# Ethernet.net
KiCad netlist of a schematic drawn in Altium Designer
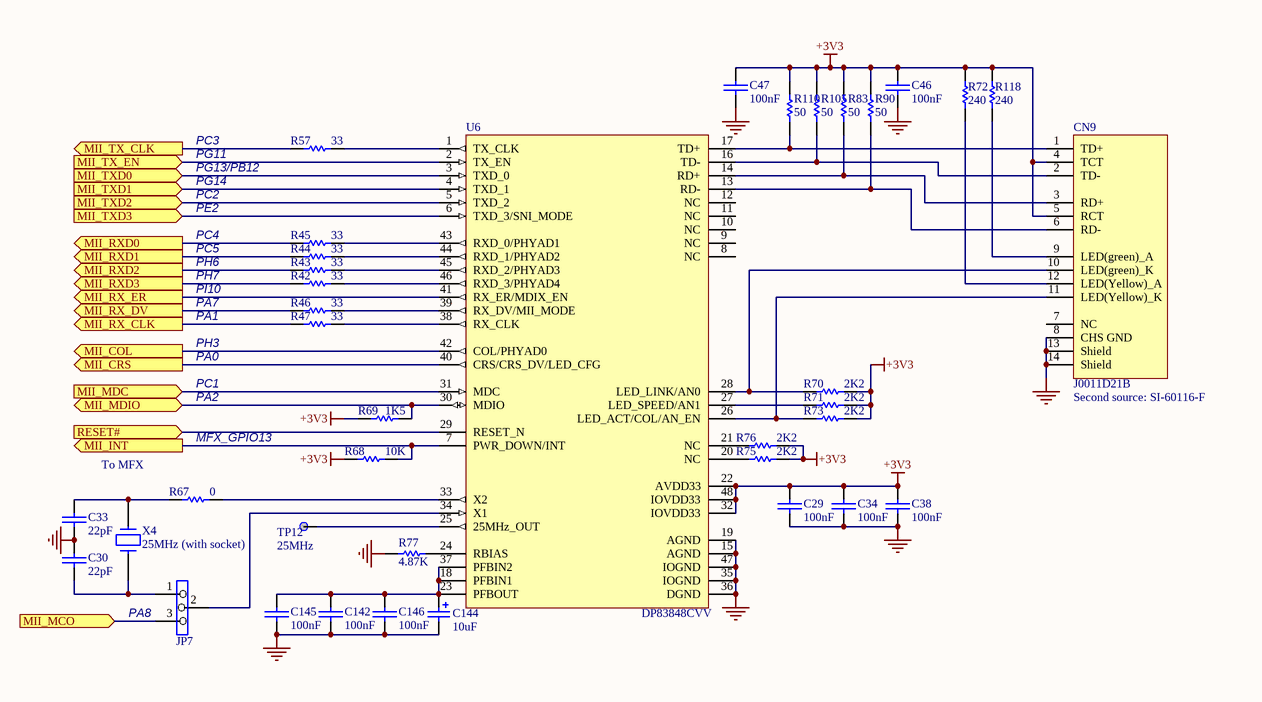
[diagram p0: Ethernet.SchDoc]

(export (version "E")
  (design (tool "Eeschema 10.0.6"))
  (components
    (comp (ref "C29")
      (value "100nF")
      (footprint "0603C")
      (description "Capacitor")
      (libsource (lib "*") (part "CAP"))
    )
    (comp (ref "C30")
      (value "22pF")
      (footprint "0603C")
      (description "Capacitor")
      (libsource (lib "*") (part "CAP"))
    )
    (comp (ref "C33")
      (value "22pF")
      (footprint "0603C")
      (description "Capacitor")
      (libsource (lib "*") (part "CAP"))
    )
    (comp (ref "C34")
      (value "100nF")
      (footprint "0603C")
      (description "Capacitor")
      (libsource (lib "*") (part "CAP"))
    )
    (comp (ref "C38")
      (value "100nF")
      (footprint "0603C")
      (description "Capacitor")
      (libsource (lib "*") (part "CAP"))
    )
    (comp (ref "C46")
      (value "100nF")
      (footprint "0603C")
      (description "Capacitor")
      (libsource (lib "*") (part "CAP"))
    )
    (comp (ref "C47")
      (value "100nF")
      (footprint "0603C")
      (description "Capacitor")
      (libsource (lib "*") (part "CAP"))
    )
    (comp (ref "C142")
      (value "100nF")
      (footprint "0603C")
      (description "Capacitor")
      (libsource (lib "*") (part "CAP"))
    )
    (comp (ref "C144")
      (value "10uF")
      (footprint "TAN-A")
      (description "Polarized Capacitor (Radial)")
      (fields (field (name "PUBLISHER") "Altium Limited"))
      (libsource (lib "Miscellaneous Devices") (part "Cap Pol1"))
    )
    (comp (ref "C145")
      (value "100nF")
      (footprint "0603C")
      (description "Capacitor")
      (libsource (lib "*") (part "CAP"))
    )
    (comp (ref "C146")
      (value "100nF")
      (footprint "0603C")
      (description "Capacitor")
      (libsource (lib "*") (part "CAP"))
    )
    (comp (ref "CN9")
      (value "J0011D21B")
      (footprint "RJ45_J0011D01BNL")
      (libsource (lib "MB784") (part "J0011D21B"))
    )
    (comp (ref "JP7") (value "~") (footprint "SIP3") (libsource (lib "STR910_SCHLIB") (part "Jumper3")))
    (comp (ref "R42")
      (value "33")
      (footprint "0603R")
      (description "Resistor")
      (fields (field (name "PUBLISHER") "Altium Limited"))
      (libsource (lib "Miscellaneous Devices") (part "Res1"))
    )
    (comp (ref "R43")
      (value "33")
      (footprint "0603R")
      (description "Resistor")
      (fields (field (name "PUBLISHER") "Altium Limited"))
      (libsource (lib "Miscellaneous Devices") (part "Res1"))
    )
    (comp (ref "R44")
      (value "33")
      (footprint "0603R")
      (description "Resistor")
      (fields (field (name "PUBLISHER") "Altium Limited"))
      (libsource (lib "Miscellaneous Devices") (part "Res1"))
    )
    (comp (ref "R45")
      (value "33")
      (footprint "0603R")
      (description "Resistor")
      (fields (field (name "PUBLISHER") "Altium Limited"))
      (libsource (lib "Miscellaneous Devices") (part "Res1"))
    )
    (comp (ref "R46")
      (value "33")
      (footprint "0603R")
      (description "Resistor")
      (fields (field (name "PUBLISHER") "Altium Limited"))
      (libsource (lib "Miscellaneous Devices") (part "Res1"))
    )
    (comp (ref "R47")
      (value "33")
      (footprint "0603R")
      (description "Resistor")
      (fields (field (name "PUBLISHER") "Altium Limited"))
      (libsource (lib "Miscellaneous Devices") (part "Res1"))
    )
    (comp (ref "R57")
      (value "33")
      (footprint "0603R")
      (description "Resistor")
      (fields (field (name "PUBLISHER") "Altium Limited"))
      (libsource (lib "Miscellaneous Devices") (part "Res1"))
    )
    (comp (ref "R67")
      (value "0")
      (footprint "0603R")
      (description "Resistor")
      (fields (field (name "PUBLISHER") "Altium Limited"))
      (libsource (lib "Miscellaneous Devices") (part "Res1"))
    )
    (comp (ref "R68")
      (value "10K")
      (footprint "0603R")
      (description "Resistor")
      (fields (field (name "PUBLISHER") "Altium Limited"))
      (libsource (lib "Miscellaneous Devices") (part "Res1"))
    )
    (comp (ref "R69")
      (value "1K5")
      (footprint "0603R")
      (description "Resistor")
      (fields (field (name "PUBLISHER") "Altium Limited"))
      (libsource (lib "Miscellaneous Devices") (part "Res1"))
    )
    (comp (ref "R70")
      (value "2K2")
      (footprint "0603R")
      (description "Resistor")
      (fields (field (name "PUBLISHER") "Altium Limited"))
      (libsource (lib "Miscellaneous Devices") (part "Res1"))
    )
    (comp (ref "R71")
      (value "2K2")
      (footprint "0603R")
      (description "Resistor")
      (fields (field (name "PUBLISHER") "Altium Limited"))
      (libsource (lib "Miscellaneous Devices") (part "Res1"))
    )
    (comp (ref "R72")
      (value "240")
      (footprint "0603R")
      (description "Resistor")
      (fields (field (name "PUBLISHER") "Altium Limited"))
      (libsource (lib "Miscellaneous Devices") (part "Res1"))
    )
    (comp (ref "R73")
      (value "2K2")
      (footprint "0603R")
      (description "Resistor")
      (fields (field (name "PUBLISHER") "Altium Limited"))
      (libsource (lib "Miscellaneous Devices") (part "Res1"))
    )
    (comp (ref "R75")
      (value "2K2")
      (footprint "0603R")
      (description "Resistor")
      (fields (field (name "PUBLISHER") "Altium Limited"))
      (libsource (lib "Miscellaneous Devices") (part "Res1"))
    )
    (comp (ref "R76")
      (value "2K2")
      (footprint "0603R")
      (description "Resistor")
      (fields (field (name "PUBLISHER") "Altium Limited"))
      (libsource (lib "Miscellaneous Devices") (part "Res1"))
    )
    (comp (ref "R77")
      (value "4.87K")
      (footprint "0603R")
      (description "Resistor")
      (fields (field (name "PUBLISHER") "Altium Limited"))
      (libsource (lib "Miscellaneous Devices") (part "Res1"))
    )
    (comp (ref "R83")
      (value "50")
      (footprint "0603R")
      (description "Resistor")
      (fields (field (name "PUBLISHER") "Altium Limited"))
      (libsource (lib "Miscellaneous Devices") (part "Res1"))
    )
    (comp (ref "R90")
      (value "50")
      (footprint "0603R")
      (description "Resistor")
      (fields (field (name "PUBLISHER") "Altium Limited"))
      (libsource (lib "Miscellaneous Devices") (part "Res1"))
    )
    (comp (ref "R105")
      (value "50")
      (footprint "0603R")
      (description "Resistor")
      (fields (field (name "PUBLISHER") "Altium Limited"))
      (libsource (lib "Miscellaneous Devices") (part "Res1"))
    )
    (comp (ref "R110")
      (value "50")
      (footprint "0603R")
      (description "Resistor")
      (fields (field (name "PUBLISHER") "Altium Limited"))
      (libsource (lib "Miscellaneous Devices") (part "Res1"))
    )
    (comp (ref "R118")
      (value "240")
      (footprint "0603R")
      (description "Resistor")
      (fields (field (name "PUBLISHER") "Altium Limited"))
      (libsource (lib "Miscellaneous Devices") (part "Res1"))
    )
    (comp (ref "TP12") (value "25MHz") (footprint "TP") (libsource (lib "*") (part "TP")))
    (comp (ref "U6")
      (value "DP83848CVV")
      (footprint "LQFP48_0R5_9X9")
      (libsource (lib "MB784") (part "DP83848CVV"))
    )
    (comp (ref "X4")
      (value "25MHz (with socket)")
      (footprint "XTAL_socket")
      (description "Crystal")
      (libsource (lib "*") (part "CRYSTAL"))
    )
  )
  (nets
    (net (code "1") (name "+3V3") (class "Default")
      (node (ref "C29") (pin "1") (pinfunction "1_1") (pintype "passive"))
      (node (ref "C34") (pin "2") (pinfunction "2_2") (pintype "passive"))
      (node (ref "C38") (pin "2") (pinfunction "2_2") (pintype "passive"))
      (node (ref "C46") (pin "2") (pinfunction "2_2") (pintype "passive"))
      (node (ref "C47") (pin "2") (pinfunction "2_2") (pintype "passive"))
      (node (ref "CN9") (pin "4") (pinfunction "TCT_4") (pintype "passive"))
      (node (ref "CN9") (pin "5") (pinfunction "RCT_5") (pintype "passive"))
      (node (ref "R105") (pin "1") (pinfunction "1_1") (pintype "passive"))
      (node (ref "R110") (pin "1") (pinfunction "1_1") (pintype "passive"))
      (node (ref "R118") (pin "2") (pinfunction "2_2") (pintype "passive"))
      (node (ref "R68") (pin "1") (pinfunction "1_1") (pintype "passive"))
      (node (ref "R69") (pin "2") (pinfunction "2_2") (pintype "passive"))
      (node (ref "R70") (pin "2") (pinfunction "2_2") (pintype "passive"))
      (node (ref "R71") (pin "2") (pinfunction "2_2") (pintype "passive"))
      (node (ref "R72") (pin "2") (pinfunction "2_2") (pintype "passive"))
      (node (ref "R73") (pin "2") (pinfunction "2_2") (pintype "passive"))
      (node (ref "R75") (pin "2") (pinfunction "2_2") (pintype "passive"))
      (node (ref "R76") (pin "2") (pinfunction "2_2") (pintype "passive"))
      (node (ref "R83") (pin "1") (pinfunction "1_1") (pintype "passive"))
      (node (ref "R90") (pin "1") (pinfunction "1_1") (pintype "passive"))
      (node (ref "U6") (pin "22") (pinfunction "AVDD33_22") (pintype "passive"))
      (node (ref "U6") (pin "32") (pinfunction "IOVDD33_32") (pintype "passive"))
      (node (ref "U6") (pin "48") (pinfunction "IOVDD33_48") (pintype "passive"))
    )
    (net (code "2") (name "/MII_COL") (class "Default")
      (node (ref "U6") (pin "42") (pinfunction "COL/PHYAD0_42") (pintype "output"))
    )
    (net (code "3") (name "/MII_CRS") (class "Default")
      (node (ref "U6") (pin "40") (pinfunction "CRS/CRS_DV/LED_CFG_40") (pintype "output"))
    )
    (net (code "4") (name "/MII_INT") (class "Default")
      (node (ref "R68") (pin "2") (pinfunction "2_2") (pintype "passive"))
      (node (ref "U6") (pin "7") (pinfunction "PWR_DOWN/INT_7") (pintype "passive"))
    )
    (net (code "5") (name "/MII_MCO") (class "Default") (node (ref "JP7") (pin "3") (pintype "passive")))
    (net (code "6") (name "/MII_MDC") (class "Default")
      (node (ref "U6") (pin "31") (pinfunction "MDC_31") (pintype "input"))
    )
    (net (code "7") (name "/MII_MDIO") (class "Default")
      (node (ref "R69") (pin "1") (pinfunction "1_1") (pintype "passive"))
      (node (ref "U6") (pin "30") (pinfunction "MDIO_30") (pintype "bidirectional"))
    )
    (net (code "8") (name "/MII_RXD0") (class "Default")
      (node (ref "R45") (pin "2") (pinfunction "2_2") (pintype "passive"))
    )
    (net (code "9") (name "/MII_RXD1") (class "Default")
      (node (ref "R44") (pin "2") (pinfunction "2_2") (pintype "passive"))
    )
    (net (code "10") (name "/MII_RXD2") (class "Default")
      (node (ref "R43") (pin "2") (pinfunction "2_2") (pintype "passive"))
    )
    (net (code "11") (name "/MII_RXD3") (class "Default")
      (node (ref "R42") (pin "2") (pinfunction "2_2") (pintype "passive"))
    )
    (net (code "12") (name "/MII_RX_CLK") (class "Default")
      (node (ref "R47") (pin "2") (pinfunction "2_2") (pintype "passive"))
    )
    (net (code "13") (name "/MII_RX_DV") (class "Default")
      (node (ref "R46") (pin "2") (pinfunction "2_2") (pintype "passive"))
    )
    (net (code "14") (name "/MII_RX_ER") (class "Default")
      (node (ref "U6") (pin "41") (pinfunction "RX_ER/MDIX_EN_41") (pintype "output"))
    )
    (net (code "15") (name "/MII_TXD0") (class "Default")
      (node (ref "U6") (pin "3") (pinfunction "TXD_0_3") (pintype "input"))
    )
    (net (code "16") (name "/MII_TXD1") (class "Default")
      (node (ref "U6") (pin "4") (pinfunction "TXD_1_4") (pintype "input"))
    )
    (net (code "17") (name "/MII_TXD2") (class "Default")
      (node (ref "U6") (pin "5") (pinfunction "TXD_2_5") (pintype "input"))
    )
    (net (code "18") (name "/MII_TXD3") (class "Default")
      (node (ref "U6") (pin "6") (pinfunction "TXD_3/SNI_MODE_6") (pintype "input"))
    )
    (net (code "19") (name "/MII_TX_CLK") (class "Default")
      (node (ref "R57") (pin "2") (pinfunction "2_2") (pintype "passive"))
    )
    (net (code "20") (name "/MII_TX_EN") (class "Default")
      (node (ref "U6") (pin "2") (pinfunction "TX_EN_2") (pintype "input"))
    )
    (net (code "21") (name "/RESET#") (class "Default")
      (node (ref "U6") (pin "29") (pinfunction "RESET_N_29") (pintype "passive"))
    )
    (net (code "22") (name "GND") (class "Default")
      (node (ref "C142") (pin "1") (pinfunction "1_1") (pintype "passive"))
      (node (ref "C144") (pin "2") (pinfunction "2_2") (pintype "passive"))
      (node (ref "C145") (pin "2") (pinfunction "2_2") (pintype "passive"))
      (node (ref "C146") (pin "1") (pinfunction "1_1") (pintype "passive"))
      (node (ref "C29") (pin "2") (pinfunction "2_2") (pintype "passive"))
      (node (ref "C30") (pin "2") (pinfunction "2_2") (pintype "passive"))
      (node (ref "C33") (pin "1") (pinfunction "1_1") (pintype "passive"))
      (node (ref "C34") (pin "1") (pinfunction "1_1") (pintype "passive"))
      (node (ref "C38") (pin "1") (pinfunction "1_1") (pintype "passive"))
      (node (ref "C46") (pin "1") (pinfunction "1_1") (pintype "passive"))
      (node (ref "C47") (pin "1") (pinfunction "1_1") (pintype "passive"))
      (node (ref "CN9") (pin "13") (pinfunction "Shield_13") (pintype "passive"))
      (node (ref "CN9") (pin "14") (pinfunction "Shield_14") (pintype "passive"))
      (node (ref "CN9") (pin "8") (pinfunction "CHS_GND_8") (pintype "passive"))
      (node (ref "R77") (pin "1") (pinfunction "1_1") (pintype "passive"))
      (node (ref "U6") (pin "15") (pinfunction "AGND_15") (pintype "passive"))
      (node (ref "U6") (pin "19") (pinfunction "AGND_19") (pintype "passive"))
      (node (ref "U6") (pin "35") (pinfunction "IOGND_35") (pintype "passive"))
      (node (ref "U6") (pin "36") (pinfunction "DGND_36") (pintype "passive"))
      (node (ref "U6") (pin "47") (pinfunction "IOGND_47") (pintype "passive"))
    )
    (net (code "23") (name "Net-(C30-Pad1)") (class "Default")
      (node (ref "C30") (pin "1") (pinfunction "1_1") (pintype "passive"))
      (node (ref "JP7") (pin "1") (pintype "passive"))
      (node (ref "X4") (pin "1") (pinfunction "1_1") (pintype "passive"))
    )
    (net (code "24") (name "Net-(C33-Pad2)") (class "Default")
      (node (ref "C33") (pin "2") (pinfunction "2_2") (pintype "passive"))
      (node (ref "R67") (pin "2") (pinfunction "2_2") (pintype "passive"))
      (node (ref "X4") (pin "2") (pinfunction "2_2") (pintype "passive"))
    )
    (net (code "25") (name "Net-(CN9-LED(Yellow)_A)") (class "Default")
      (node (ref "CN9") (pin "12") (pinfunction "LED(Yellow)_A_12") (pintype "passive"))
      (node (ref "R72") (pin "1") (pinfunction "1_1") (pintype "passive"))
    )
    (net (code "26") (name "Net-(CN9-LED(Yellow)_K)") (class "Default")
      (node (ref "CN9") (pin "11") (pinfunction "LED(Yellow)_K_11") (pintype "passive"))
      (node (ref "R73") (pin "1") (pinfunction "1_1") (pintype "passive"))
      (node (ref "U6") (pin "26") (pinfunction "LED_ACT/COL/AN_EN_26") (pintype "passive"))
    )
    (net (code "27") (name "Net-(CN9-LED(green)_A)") (class "Default")
      (node (ref "CN9") (pin "9") (pinfunction "LED(green)_A_9") (pintype "passive"))
      (node (ref "R118") (pin "1") (pinfunction "1_1") (pintype "passive"))
    )
    (net (code "28") (name "Net-(CN9-LED(green)_K)") (class "Default")
      (node (ref "CN9") (pin "10") (pinfunction "LED(green)_K_10") (pintype "passive"))
      (node (ref "R70") (pin "1") (pinfunction "1_1") (pintype "passive"))
      (node (ref "U6") (pin "28") (pinfunction "LED_LINK/AN0_28") (pintype "passive"))
    )
    (net (code "29") (name "Net-(CN9-RD+)") (class "Default")
      (node (ref "CN9") (pin "3") (pinfunction "RD+_3") (pintype "passive"))
      (node (ref "R83") (pin "2") (pinfunction "2_2") (pintype "passive"))
      (node (ref "U6") (pin "14") (pinfunction "RD+_14") (pintype "passive"))
    )
    (net (code "30") (name "Net-(CN9-RD-)") (class "Default")
      (node (ref "CN9") (pin "6") (pinfunction "RD-_6") (pintype "passive"))
      (node (ref "R90") (pin "2") (pinfunction "2_2") (pintype "passive"))
      (node (ref "U6") (pin "13") (pinfunction "RD-_13") (pintype "passive"))
    )
    (net (code "31") (name "Net-(CN9-TD+)") (class "Default")
      (node (ref "CN9") (pin "1") (pinfunction "TD+_1") (pintype "passive"))
      (node (ref "R110") (pin "2") (pinfunction "2_2") (pintype "passive"))
      (node (ref "U6") (pin "17") (pinfunction "TD+_17") (pintype "passive"))
    )
    (net (code "32") (name "Net-(CN9-TD-)") (class "Default")
      (node (ref "CN9") (pin "2") (pinfunction "TD-_2") (pintype "passive"))
      (node (ref "R105") (pin "2") (pinfunction "2_2") (pintype "passive"))
      (node (ref "U6") (pin "16") (pinfunction "TD-_16") (pintype "passive"))
    )
    (net (code "33") (name "Net-(R75-Pad1)") (class "Default")
      (node (ref "R75") (pin "1") (pinfunction "1_1") (pintype "passive"))
      (node (ref "U6") (pin "20") (pinfunction "NC_20") (pintype "passive"))
    )
    (net (code "34") (name "Net-(R76-Pad1)") (class "Default")
      (node (ref "R76") (pin "1") (pinfunction "1_1") (pintype "passive"))
      (node (ref "U6") (pin "21") (pinfunction "NC_21") (pintype "passive"))
    )
    (net (code "35") (name "Net-(U6-25MHz_OUT)") (class "Default")
      (node (ref "TP12") (pin "1") (pinfunction "1_1") (pintype "passive"))
      (node (ref "U6") (pin "25") (pinfunction "25MHz_OUT_25") (pintype "output"))
    )
    (net (code "36") (name "Net-(U6-LED_SPEED{slash}AN1)") (class "Default")
      (node (ref "R71") (pin "1") (pinfunction "1_1") (pintype "passive"))
      (node (ref "U6") (pin "27") (pinfunction "LED_SPEED/AN1_27") (pintype "passive"))
    )
    (net (code "37") (name "Net-(U6-PFBIN1)") (class "Default")
      (node (ref "C142") (pin "2") (pinfunction "2_2") (pintype "passive"))
      (node (ref "C144") (pin "1") (pinfunction "1_1") (pintype "passive"))
      (node (ref "C145") (pin "1") (pinfunction "1_1") (pintype "passive"))
      (node (ref "C146") (pin "2") (pinfunction "2_2") (pintype "passive"))
      (node (ref "U6") (pin "18") (pinfunction "PFBIN1_18") (pintype "passive"))
      (node (ref "U6") (pin "23") (pinfunction "PFBOUT_23") (pintype "passive"))
      (node (ref "U6") (pin "37") (pinfunction "PFBIN2_37") (pintype "passive"))
    )
    (net (code "38") (name "Net-(U6-RBIAS)") (class "Default")
      (node (ref "R77") (pin "2") (pinfunction "2_2") (pintype "passive"))
      (node (ref "U6") (pin "24") (pinfunction "RBIAS_24") (pintype "passive"))
    )
    (net (code "39") (name "Net-(U6-RXD_0{slash}PHYAD1)") (class "Default")
      (node (ref "R45") (pin "1") (pinfunction "1_1") (pintype "passive"))
      (node (ref "U6") (pin "43") (pinfunction "RXD_0/PHYAD1_43") (pintype "output"))
    )
    (net (code "40") (name "Net-(U6-RXD_1{slash}PHYAD2)") (class "Default")
      (node (ref "R44") (pin "1") (pinfunction "1_1") (pintype "passive"))
      (node (ref "U6") (pin "44") (pinfunction "RXD_1/PHYAD2_44") (pintype "output"))
    )
    (net (code "41") (name "Net-(U6-RXD_2{slash}PHYAD3)") (class "Default")
      (node (ref "R43") (pin "1") (pinfunction "1_1") (pintype "passive"))
      (node (ref "U6") (pin "45") (pinfunction "RXD_2/PHYAD3_45") (pintype "output"))
    )
    (net (code "42") (name "Net-(U6-RXD_3{slash}PHYAD4)") (class "Default")
      (node (ref "R42") (pin "1") (pinfunction "1_1") (pintype "passive"))
      (node (ref "U6") (pin "46") (pinfunction "RXD_3/PHYAD4_46") (pintype "output"))
    )
    (net (code "43") (name "Net-(U6-RX_CLK)") (class "Default")
      (node (ref "R47") (pin "1") (pinfunction "1_1") (pintype "passive"))
      (node (ref "U6") (pin "38") (pinfunction "RX_CLK_38") (pintype "output"))
    )
    (net (code "44") (name "Net-(U6-RX_DV{slash}MII_MODE)") (class "Default")
      (node (ref "R46") (pin "1") (pinfunction "1_1") (pintype "passive"))
      (node (ref "U6") (pin "39") (pinfunction "RX_DV/MII_MODE_39") (pintype "output"))
    )
    (net (code "45") (name "Net-(U6-TX_CLK)") (class "Default")
      (node (ref "R57") (pin "1") (pinfunction "1_1") (pintype "passive"))
      (node (ref "U6") (pin "1") (pinfunction "TX_CLK_1") (pintype "output"))
    )
    (net (code "46") (name "Net-(U6-X1)") (class "Default")
      (node (ref "JP7") (pin "2") (pintype "passive"))
      (node (ref "U6") (pin "34") (pinfunction "X1_34") (pintype "input"))
    )
    (net (code "47") (name "Net-(U6-X2)") (class "Default")
      (node (ref "R67") (pin "1") (pinfunction "1_1") (pintype "passive"))
      (node (ref "U6") (pin "33") (pinfunction "X2_33") (pintype "output"))
    )
    (net (code "48") (name "unconnected-(CN9-NC-Pad7)") (class "Default")
      (node (ref "CN9") (pin "7") (pinfunction "NC_7") (pintype "passive"))
    )
    (net (code "49") (name "unconnected-(U6-NC-Pad8)") (class "Default")
      (node (ref "U6") (pin "8") (pinfunction "NC_8") (pintype "passive"))
    )
    (net (code "50") (name "unconnected-(U6-NC-Pad9)") (class "Default")
      (node (ref "U6") (pin "9") (pinfunction "NC_9") (pintype "passive"))
    )
    (net (code "51") (name "unconnected-(U6-NC-Pad10)") (class "Default")
      (node (ref "U6") (pin "10") (pinfunction "NC_10") (pintype "passive"))
    )
    (net (code "52") (name "unconnected-(U6-NC-Pad11)") (class "Default")
      (node (ref "U6") (pin "11") (pinfunction "NC_11") (pintype "passive"))
    )
    (net (code "53") (name "unconnected-(U6-NC-Pad12)") (class "Default")
      (node (ref "U6") (pin "12") (pinfunction "NC_12") (pintype "passive"))
    )
  )
)
